# LPCB235_-_AUX_POWER.net
KiCad netlist of a schematic drawn in Altium Designer
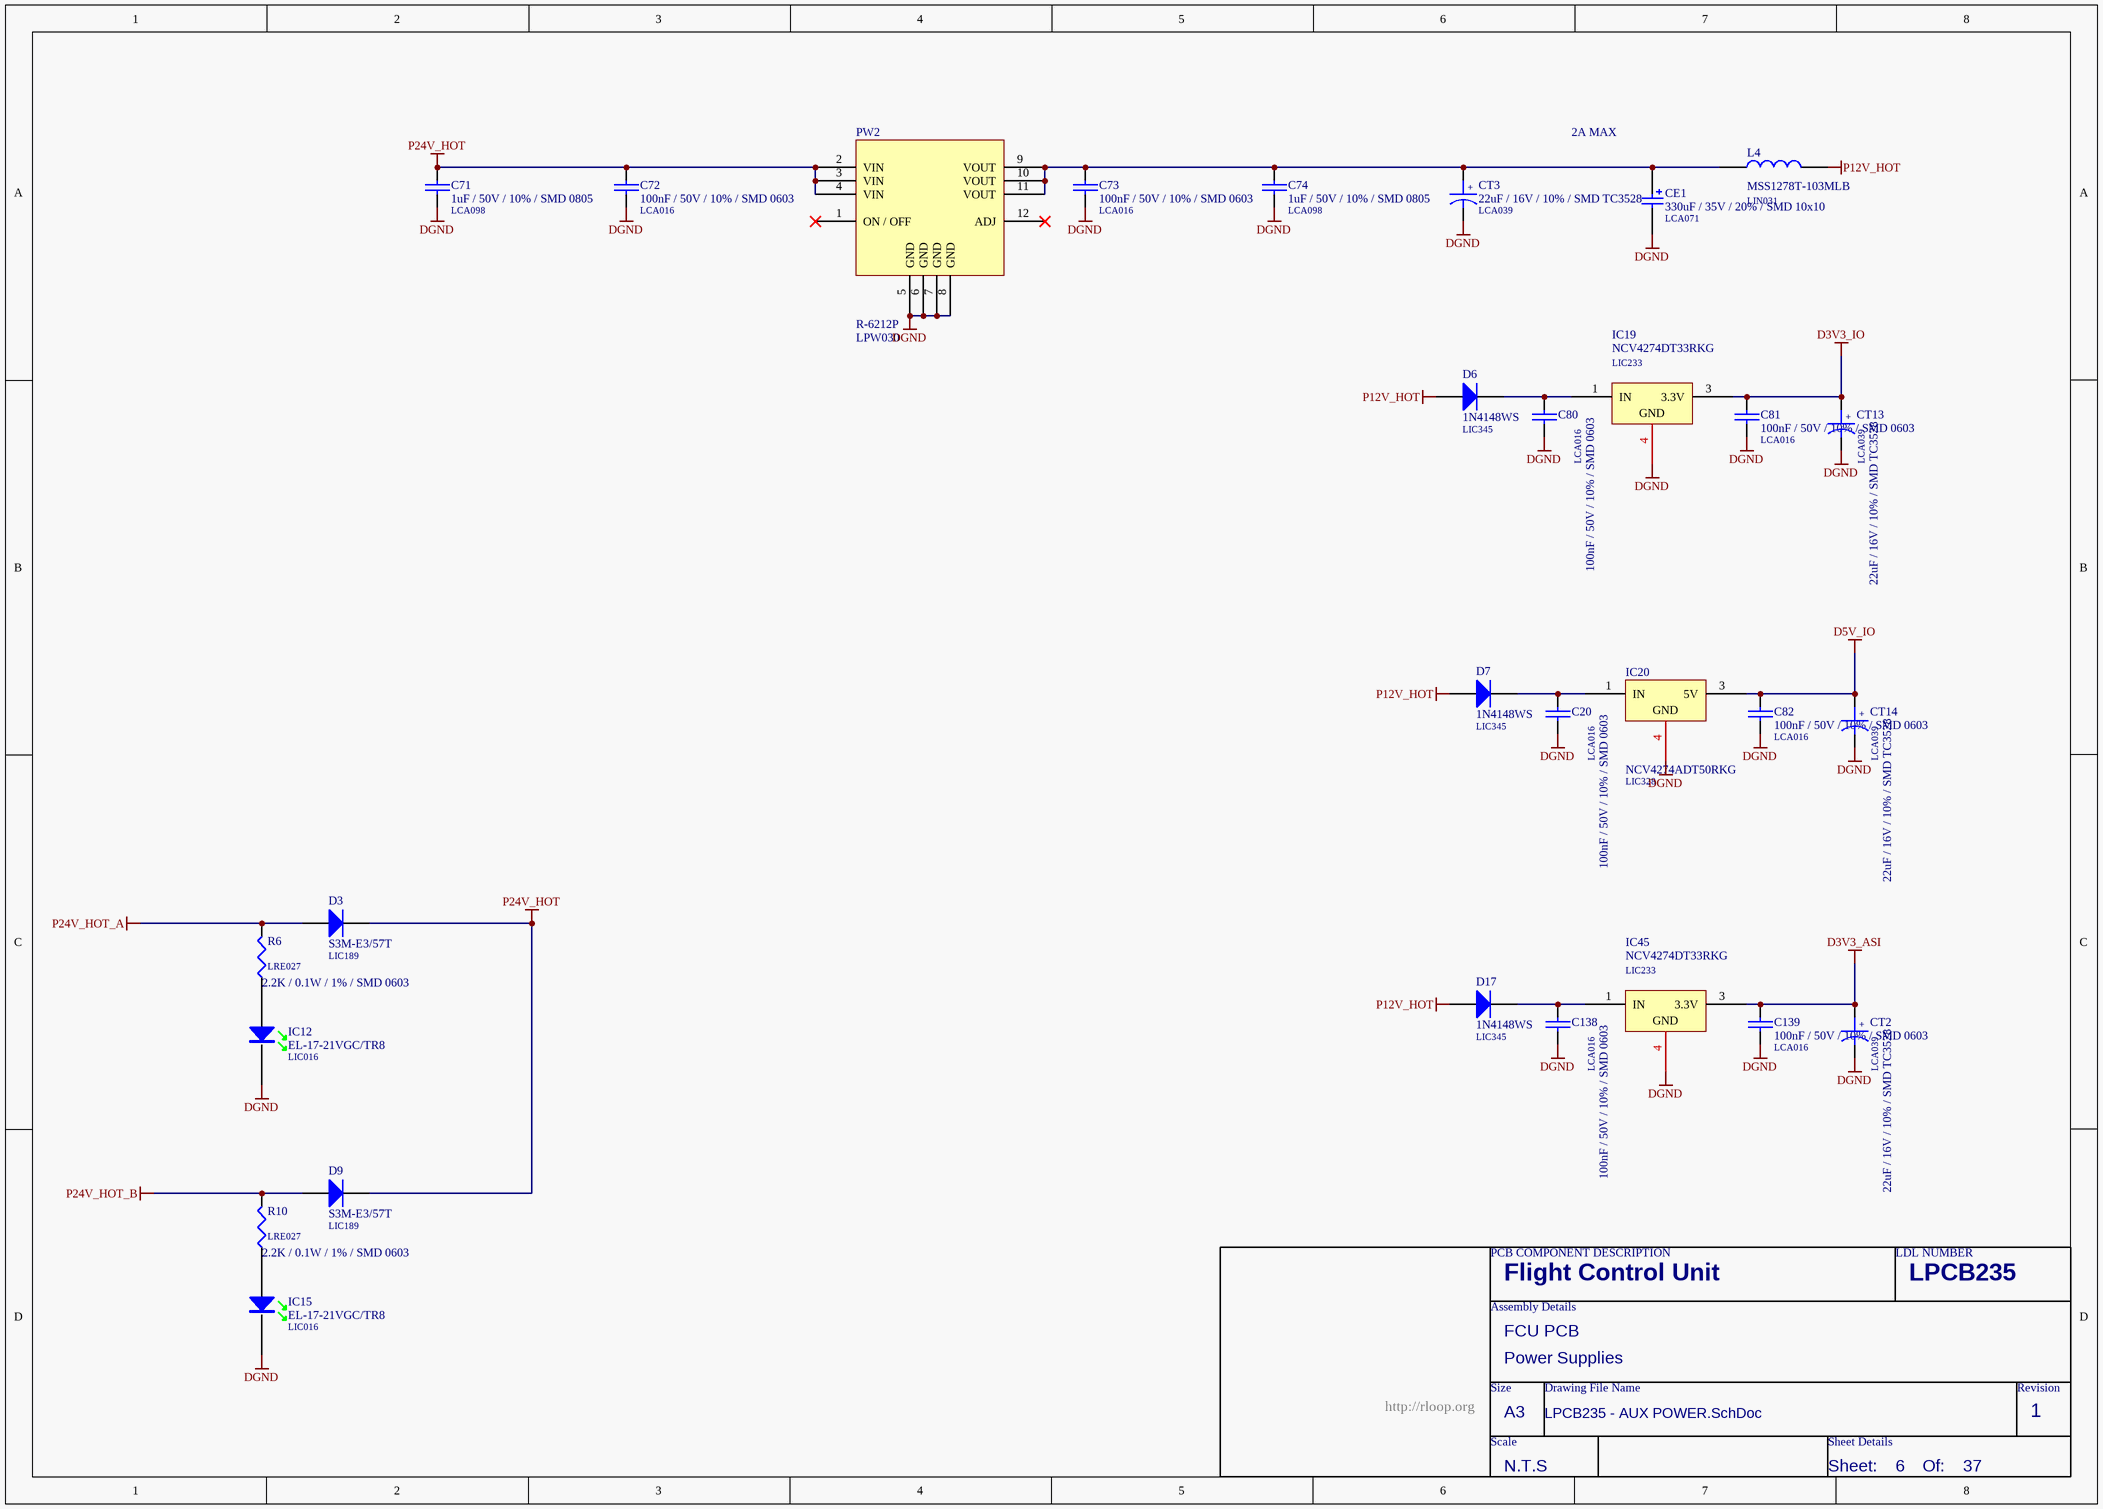
[diagram p0: LPCB235 - AUX POWER.SchDoc]

(export (version "E")
  (design (tool "Eeschema 10.0.6"))
  (components
    (comp (ref "C20")
      (value "100nF / 50V / 10% / SMD 0603")
      (footprint "LFP011__CC1608-0603-IPC7351_B")
      (description "Capacitor, Ceramic Chip, 100nF (0.1uF), 50V, 5%, SMD 0603 [LCA016]")
      (fields (field (name "LDL_NUMBER") "LCA016"))
      (libsource (lib "LDL_Capacitors") (part "100nF / 50V / 10% / SMD 0603"))
    )
    (comp (ref "C71")
      (value "1uF / 50V / 10% / SMD 0805")
      (footprint "LFP010__CC2012-0805-IPC7351_B")
      (description "Capacitor, Ceramic Chip, 1uF, 50V, SMD 0805 [LCA098]")
      (fields (field (name "LDL_NUMBER") "LCA098"))
      (libsource (lib "LDL_Capacitors") (part "1uF / 50V / 10% / SMD 0805"))
    )
    (comp (ref "C72")
      (value "100nF / 50V / 10% / SMD 0603")
      (footprint "LFP011__CC1608-0603-IPC7351_B")
      (description "Capacitor, Ceramic Chip, 100nF (0.1uF), 50V, 5%, SMD 0603 [LCA016]")
      (fields (field (name "LDL_NUMBER") "LCA016"))
      (libsource (lib "LDL_Capacitors") (part "100nF / 50V / 10% / SMD 0603"))
    )
    (comp (ref "C73")
      (value "100nF / 50V / 10% / SMD 0603")
      (footprint "LFP011__CC1608-0603-IPC7351_B")
      (description "Capacitor, Ceramic Chip, 100nF (0.1uF), 50V, 5%, SMD 0603 [LCA016]")
      (fields (field (name "LDL_NUMBER") "LCA016"))
      (libsource (lib "LDL_Capacitors") (part "100nF / 50V / 10% / SMD 0603"))
    )
    (comp (ref "C74")
      (value "1uF / 50V / 10% / SMD 0805")
      (footprint "LFP010__CC2012-0805-IPC7351_B")
      (description "Capacitor, Ceramic Chip, 1uF, 50V, SMD 0805 [LCA098]")
      (fields (field (name "LDL_NUMBER") "LCA098"))
      (libsource (lib "LDL_Capacitors") (part "1uF / 50V / 10% / SMD 0805"))
    )
    (comp (ref "C80")
      (value "100nF / 50V / 10% / SMD 0603")
      (footprint "LFP011__CC1608-0603-IPC7351_B")
      (description "Capacitor, Ceramic Chip, 100nF (0.1uF), 50V, 5%, SMD 0603 [LCA016]")
      (fields (field (name "LDL_NUMBER") "LCA016"))
      (libsource (lib "LDL_Capacitors") (part "100nF / 50V / 10% / SMD 0603"))
    )
    (comp (ref "C81")
      (value "100nF / 50V / 10% / SMD 0603")
      (footprint "LFP011__CC1608-0603-IPC7351_B")
      (description "Capacitor, Ceramic Chip, 100nF (0.1uF), 50V, 5%, SMD 0603 [LCA016]")
      (fields (field (name "LDL_NUMBER") "LCA016"))
      (libsource (lib "LDL_Capacitors") (part "100nF / 50V / 10% / SMD 0603"))
    )
    (comp (ref "C82")
      (value "100nF / 50V / 10% / SMD 0603")
      (footprint "LFP011__CC1608-0603-IPC7351_B")
      (description "Capacitor, Ceramic Chip, 100nF (0.1uF), 50V, 5%, SMD 0603 [LCA016]")
      (fields (field (name "LDL_NUMBER") "LCA016"))
      (libsource (lib "LDL_Capacitors") (part "100nF / 50V / 10% / SMD 0603"))
    )
    (comp (ref "C138")
      (value "100nF / 50V / 10% / SMD 0603")
      (footprint "LFP011__CC1608-0603-IPC7351_B")
      (description "Capacitor, Ceramic Chip, 100nF (0.1uF), 50V, 5%, SMD 0603 [LCA016]")
      (fields (field (name "LDL_NUMBER") "LCA016"))
      (libsource (lib "LDL_Capacitors") (part "100nF / 50V / 10% / SMD 0603"))
    )
    (comp (ref "C139")
      (value "100nF / 50V / 10% / SMD 0603")
      (footprint "LFP011__CC1608-0603-IPC7351_B")
      (description "Capacitor, Ceramic Chip, 100nF (0.1uF), 50V, 5%, SMD 0603 [LCA016]")
      (fields (field (name "LDL_NUMBER") "LCA016"))
      (libsource (lib "LDL_Capacitors") (part "100nF / 50V / 10% / SMD 0603"))
    )
    (comp (ref "CE1")
      (value "330uF / 35V / 20% / SMD 10x10")
      (footprint "LFP041__NICHICON_WT_10X10")
      (description "Capacitor, Aluminum Electrolytic, 330uF, 35V, 20%, SMD (10mm x 10mm) [LCA071]")
      (fields (field (name "LDL_NUMBER") "LCA071"))
      (libsource (lib "LDL_Capacitors") (part "330uF / 35V / 20% / SMD 10x10"))
    )
    (comp (ref "CT2")
      (value "22uF / 16V / 10% / SMD TC3528")
      (footprint "LFP018__TC3528")
      (description "Capacitor, Tantalum, 22uF, 16V, 10%, SMD TC3528 (BCASE) [LCA039]")
      (fields (field (name "LDL_NUMBER") "LCA039"))
      (libsource (lib "LDL_Capacitors") (part "22uF / 16V / 10% / SMD TC3528"))
    )
    (comp (ref "CT3")
      (value "22uF / 16V / 10% / SMD TC3528")
      (footprint "LFP018__TC3528")
      (description "Capacitor, Tantalum, 22uF, 16V, 10%, SMD TC3528 (BCASE) [LCA039]")
      (fields (field (name "LDL_NUMBER") "LCA039"))
      (libsource (lib "LDL_Capacitors") (part "22uF / 16V / 10% / SMD TC3528"))
    )
    (comp (ref "CT13")
      (value "22uF / 16V / 10% / SMD TC3528")
      (footprint "LFP018__TC3528")
      (description "Capacitor, Tantalum, 22uF, 16V, 10%, SMD TC3528 (BCASE) [LCA039]")
      (fields (field (name "LDL_NUMBER") "LCA039"))
      (libsource (lib "LDL_Capacitors") (part "22uF / 16V / 10% / SMD TC3528"))
    )
    (comp (ref "CT14")
      (value "22uF / 16V / 10% / SMD TC3528")
      (footprint "LFP018__TC3528")
      (description "Capacitor, Tantalum, 22uF, 16V, 10%, SMD TC3528 (BCASE) [LCA039]")
      (fields (field (name "LDL_NUMBER") "LCA039"))
      (libsource (lib "LDL_Capacitors") (part "22uF / 16V / 10% / SMD TC3528"))
    )
    (comp (ref "D3")
      (value "S3M-E3/57T")
      (footprint "LFP040__DO-214AB")
      (description "Diode, General Purpose Rectifier, 3A, 200V, SMD DO-214AB [LIC189]")
      (fields (field (name "LDL_NUMBER") "LIC189"))
      (libsource (lib "LDL_Semiconductors") (part "S3M-E3/57T"))
    )
    (comp (ref "D6")
      (value "1N4148WS")
      (footprint "LFP001__SOD-323F")
      (description "Diode, Small Signal, SMD SOD-323F [LIC345]")
      (fields (field (name "LDL_NUMBER") "LIC345"))
      (libsource (lib "LDL_Semiconductors") (part "1N4148WS"))
    )
    (comp (ref "D7")
      (value "1N4148WS")
      (footprint "LFP001__SOD-323F")
      (description "Diode, Small Signal, SMD SOD-323F [LIC345]")
      (fields (field (name "LDL_NUMBER") "LIC345"))
      (libsource (lib "LDL_Semiconductors") (part "1N4148WS"))
    )
    (comp (ref "D9")
      (value "S3M-E3/57T")
      (footprint "LFP040__DO-214AB")
      (description "Diode, General Purpose Rectifier, 3A, 200V, SMD DO-214AB [LIC189]")
      (fields (field (name "LDL_NUMBER") "LIC189"))
      (libsource (lib "LDL_Semiconductors") (part "S3M-E3/57T"))
    )
    (comp (ref "D17")
      (value "1N4148WS")
      (footprint "LFP001__SOD-323F")
      (description "Diode, Small Signal, SMD SOD-323F [LIC345]")
      (fields (field (name "LDL_NUMBER") "LIC345"))
      (libsource (lib "LDL_Semiconductors") (part "1N4148WS"))
    )
    (comp (ref "IC12")
      (value "EL-17-21VGC/TR8")
      (footprint "CR2012-0805-LED")
      (description "LED, SMD, 0805 Green [LIC016]")
      (fields (field (name "LDL_NUMBER") "LIC016"))
      (libsource (lib "LDL_Semiconductors") (part "EL-17-21VGC/TR8"))
    )
    (comp (ref "IC15")
      (value "EL-17-21VGC/TR8")
      (footprint "CR2012-0805-LED")
      (description "LED, SMD, 0805 Green [LIC016]")
      (fields (field (name "LDL_NUMBER") "LIC016"))
      (libsource (lib "LDL_Semiconductors") (part "EL-17-21VGC/TR8"))
    )
    (comp (ref "IC19")
      (value "NCV4274DT33RKG")
      (footprint "LFP019__369A-13")
      (description "IC, Voltage Regulator, 400mA, 3.3V LDO, SMD DPAK [LIC233]")
      (fields (field (name "LDL_NUMBER") "LIC233"))
      (libsource (lib "LDL_Semiconductors") (part "NCV4274DT33RKG"))
    )
    (comp (ref "IC20")
      (value "NCV4274ADT50RKG")
      (footprint "LFP019__369A-13")
      (description "IC, Voltage Regulator, 400mA, 5V LDO, SMD DPAK [LIC328]")
      (fields (field (name "LDL_NUMBER") "LIC328"))
      (libsource (lib "LDL_Semiconductors") (part "NCV4274ADT50RKG"))
    )
    (comp (ref "IC45")
      (value "NCV4274DT33RKG")
      (footprint "LFP019__369A-13")
      (description "IC, Voltage Regulator, 400mA, 3.3V LDO, SMD DPAK [LIC233]")
      (fields (field (name "LDL_NUMBER") "LIC233"))
      (libsource (lib "LDL_Semiconductors") (part "NCV4274DT33RKG"))
    )
    (comp (ref "L4")
      (value "MSS1278T-103MLB")
      (footprint "LFP037__MSS1278T")
      (description "Inductor, 10uH, 20%, 5.7A, SMD [LIN031]")
      (fields (field (name "LDL_NUMBER") "LIN031"))
      (libsource (lib "LDL_Inductors") (part "MSS1278T-103MLB"))
    )
    (comp (ref "PW2")
      (value "R-6212P")
      (footprint "R-625.0P")
      (description "Non Isolated DC/DC Module")
      (fields (field (name "LDL_NUMBER") "LPW030"))
      (libsource (lib "LDL_Power") (part "R-6212P"))
    )
    (comp (ref "R6")
      (value "2.2K / 0.1W / 1% / SMD 0603")
      (footprint "LFP020__CR1608-0603-IPC7351_B")
      (description "Resistor, Ceramic Chip, 2.2K, 0.1W, 1%, SMD 0603 [LRE027]")
      (fields (field (name "LDL_NUMBER") "LRE027"))
      (libsource (lib "LDL_Resistors") (part "2.2K / 0.1W / 1% / SMD 0603"))
    )
    (comp (ref "R10")
      (value "2.2K / 0.1W / 1% / SMD 0603")
      (footprint "LFP020__CR1608-0603-IPC7351_B")
      (description "Resistor, Ceramic Chip, 2.2K, 0.1W, 1%, SMD 0603 [LRE027]")
      (fields (field (name "LDL_NUMBER") "LRE027"))
      (libsource (lib "LDL_Resistors") (part "2.2K / 0.1W / 1% / SMD 0603"))
    )
  )
  (nets
    (net (code "1") (name "D3V3_ASI") (class "Default")
      (node (ref "C139") (pin "1") (pintype "passive"))
      (node (ref "CT2") (pin "1") (pinfunction "1_1") (pintype "passive"))
      (node (ref "IC45") (pin "3") (pinfunction "3.3V_3") (pintype "power_in"))
    )
    (net (code "2") (name "D3V3_IO") (class "Default")
      (node (ref "C81") (pin "1") (pintype "passive"))
      (node (ref "CT13") (pin "1") (pinfunction "1_1") (pintype "passive"))
      (node (ref "IC19") (pin "3") (pinfunction "3.3V_3") (pintype "power_in"))
    )
    (net (code "3") (name "D5V_IO") (class "Default")
      (node (ref "C82") (pin "1") (pintype "passive"))
      (node (ref "CT14") (pin "1") (pinfunction "1_1") (pintype "passive"))
      (node (ref "IC20") (pin "3") (pinfunction "5V_3") (pintype "power_in"))
    )
    (net (code "4") (name "DGND") (class "Default")
      (node (ref "C138") (pin "2") (pintype "passive"))
      (node (ref "C139") (pin "2") (pintype "passive"))
      (node (ref "C20") (pin "2") (pintype "passive"))
      (node (ref "C71") (pin "2") (pintype "passive"))
      (node (ref "C72") (pin "2") (pintype "passive"))
      (node (ref "C73") (pin "2") (pintype "passive"))
      (node (ref "C74") (pin "2") (pintype "passive"))
      (node (ref "C80") (pin "2") (pintype "passive"))
      (node (ref "C81") (pin "2") (pintype "passive"))
      (node (ref "C82") (pin "2") (pintype "passive"))
      (node (ref "CE1") (pin "2") (pinfunction "2_2") (pintype "passive"))
      (node (ref "CT13") (pin "2") (pinfunction "2_2") (pintype "passive"))
      (node (ref "CT14") (pin "2") (pinfunction "2_2") (pintype "passive"))
      (node (ref "CT2") (pin "2") (pinfunction "2_2") (pintype "passive"))
      (node (ref "CT3") (pin "2") (pinfunction "2_2") (pintype "passive"))
      (node (ref "IC12") (pin "K") (pintype "passive"))
      (node (ref "IC15") (pin "K") (pintype "passive"))
      (node (ref "IC19") (pin "4") (pinfunction "GND_4") (pintype "power_in"))
      (node (ref "IC20") (pin "4") (pinfunction "ADJ_4") (pintype "power_in"))
      (node (ref "IC45") (pin "4") (pinfunction "GND_4") (pintype "power_in"))
      (node (ref "PW2") (pin "5") (pinfunction "GND_5") (pintype "power_in"))
      (node (ref "PW2") (pin "6") (pinfunction "GND_6") (pintype "power_in"))
      (node (ref "PW2") (pin "7") (pinfunction "GND_7") (pintype "power_in"))
      (node (ref "PW2") (pin "8") (pinfunction "GND_8") (pintype "power_in"))
    )
    (net (code "5") (name "Net-(C73-Pad1)") (class "Default")
      (node (ref "C73") (pin "1") (pintype "passive"))
      (node (ref "C74") (pin "1") (pintype "passive"))
      (node (ref "CE1") (pin "1") (pinfunction "1_1") (pintype "passive"))
      (node (ref "CT3") (pin "1") (pinfunction "1_1") (pintype "passive"))
      (node (ref "L4") (pin "1") (pinfunction "1_1") (pintype "passive"))
      (node (ref "PW2") (pin "10") (pinfunction "VOUT_10") (pintype "power_in"))
      (node (ref "PW2") (pin "11") (pinfunction "VOUT_11") (pintype "power_in"))
      (node (ref "PW2") (pin "9") (pinfunction "VOUT_9") (pintype "power_in"))
    )
    (net (code "6") (name "Net-(D6-K)") (class "Default")
      (node (ref "C80") (pin "1") (pintype "passive"))
      (node (ref "D6") (pin "1") (pinfunction "K_1") (pintype "passive"))
      (node (ref "IC19") (pin "1") (pinfunction "IN_1") (pintype "power_in"))
    )
    (net (code "7") (name "Net-(D7-K)") (class "Default")
      (node (ref "C20") (pin "1") (pintype "passive"))
      (node (ref "D7") (pin "1") (pinfunction "K_1") (pintype "passive"))
      (node (ref "IC20") (pin "1") (pinfunction "IN_1") (pintype "power_in"))
    )
    (net (code "8") (name "Net-(D17-K)") (class "Default")
      (node (ref "C138") (pin "1") (pintype "passive"))
      (node (ref "D17") (pin "1") (pinfunction "K_1") (pintype "passive"))
      (node (ref "IC45") (pin "1") (pinfunction "IN_1") (pintype "power_in"))
    )
    (net (code "9") (name "Net-(IC12-PadA)") (class "Default")
      (node (ref "IC12") (pin "A") (pintype "passive"))
      (node (ref "R6") (pin "1") (pintype "passive"))
    )
    (net (code "10") (name "Net-(IC15-PadA)") (class "Default")
      (node (ref "IC15") (pin "A") (pintype "passive"))
      (node (ref "R10") (pin "1") (pintype "passive"))
    )
    (net (code "11") (name "P12V_HOT") (class "Default")
      (node (ref "D17") (pin "2") (pinfunction "A_2") (pintype "passive"))
      (node (ref "D6") (pin "2") (pinfunction "A_2") (pintype "passive"))
      (node (ref "D7") (pin "2") (pinfunction "A_2") (pintype "passive"))
      (node (ref "L4") (pin "2") (pinfunction "2_2") (pintype "passive"))
    )
    (net (code "12") (name "P24V_HOT") (class "Default")
      (node (ref "C71") (pin "1") (pintype "passive"))
      (node (ref "C72") (pin "1") (pintype "passive"))
      (node (ref "D3") (pin "1") (pinfunction "K_1") (pintype "passive"))
      (node (ref "D9") (pin "1") (pinfunction "K_1") (pintype "passive"))
      (node (ref "PW2") (pin "2") (pinfunction "VIN_2") (pintype "power_in"))
      (node (ref "PW2") (pin "3") (pinfunction "VIN_3") (pintype "power_in"))
      (node (ref "PW2") (pin "4") (pinfunction "VIN_4") (pintype "power_in"))
    )
    (net (code "13") (name "P24V_HOT_A") (class "Default")
      (node (ref "D3") (pin "2") (pinfunction "A_2") (pintype "passive"))
      (node (ref "R6") (pin "2") (pintype "passive"))
    )
    (net (code "14") (name "P24V_HOT_B") (class "Default")
      (node (ref "D9") (pin "2") (pinfunction "A_2") (pintype "passive"))
      (node (ref "R10") (pin "2") (pintype "passive"))
    )
    (net (code "15") (name "unconnected-(PW2-ADJ-Pad12)") (class "Default")
      (node (ref "PW2") (pin "12") (pinfunction "ADJ_12") (pintype "passive+no_connect"))
    )
    (net (code "16") (name "unconnected-(PW2-ON_{slash}_OFF-Pad1)") (class "Default")
      (node (ref "PW2") (pin "1") (pinfunction "ON_/_OFF_1") (pintype "passive+no_connect"))
    )
  )
)
